# 20key.net
KiCad netlist of a schematic drawn in Altium Designer
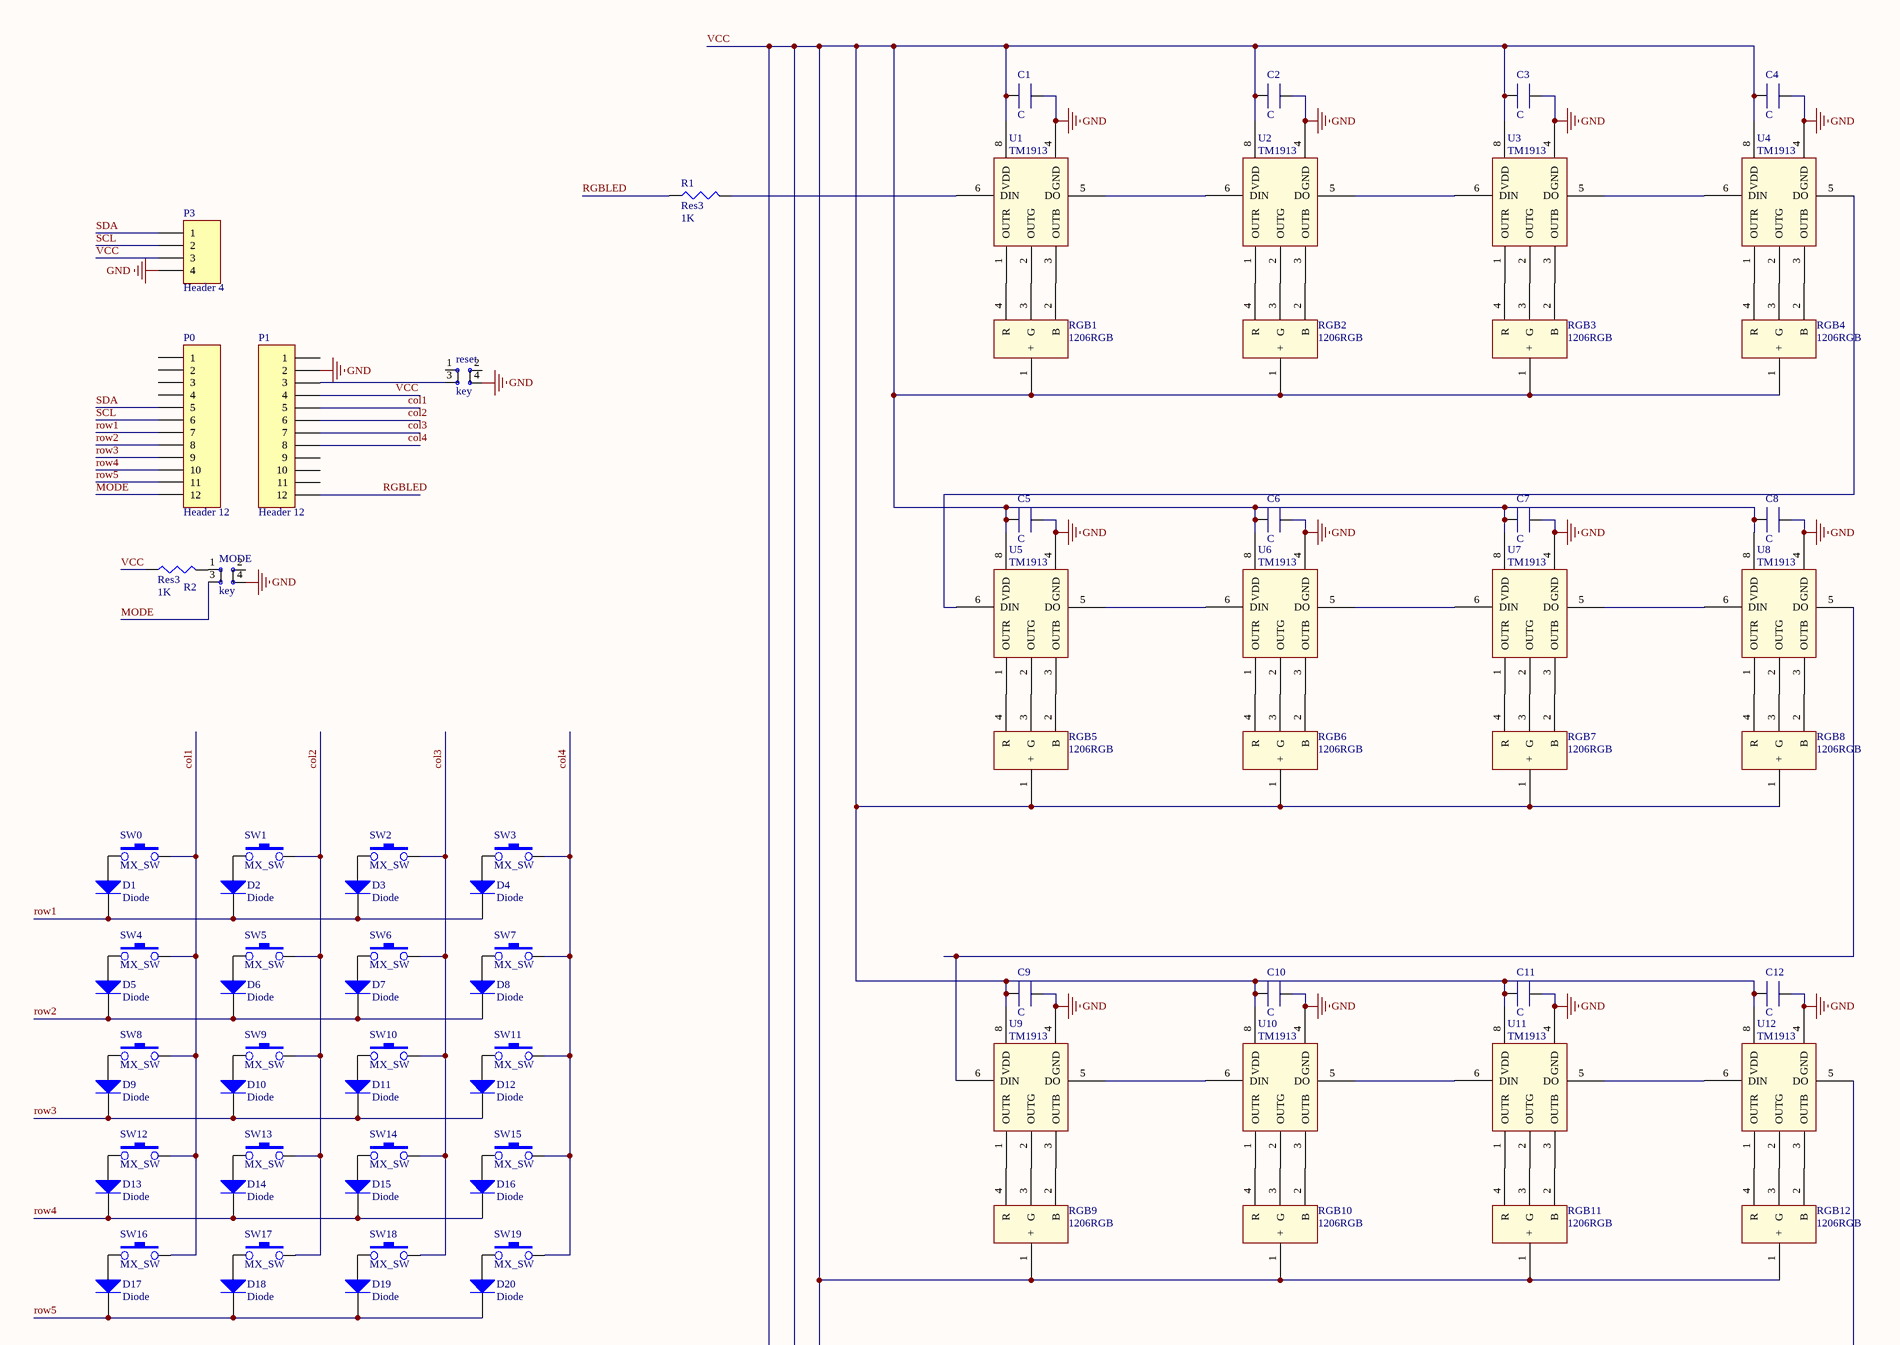
[diagram p0: 20key.SchDoc, top]
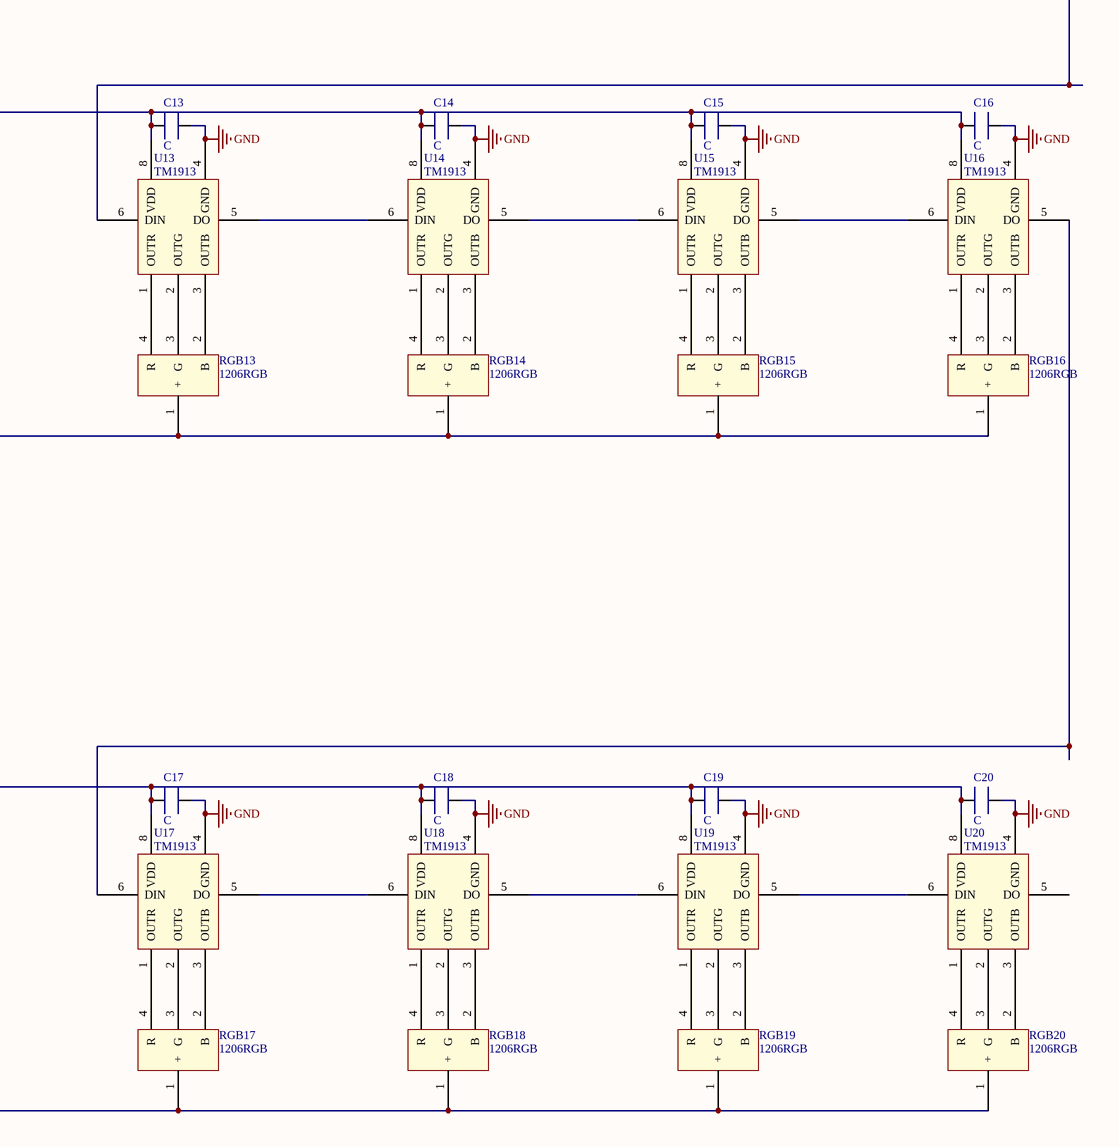
[diagram p1: 20key.SchDoc, bottom]

(export (version "E")
  (design (tool "Eeschema 10.0.6"))
  (components
    (comp (ref "C1") (value "C") (footprint "PCBComponent_1") (libsource (lib "20key") (part "C")))
    (comp (ref "C2") (value "C") (footprint "PCBComponent_1") (libsource (lib "20key") (part "C")))
    (comp (ref "C3") (value "C") (footprint "PCBComponent_1") (libsource (lib "20key") (part "C")))
    (comp (ref "C4") (value "C") (footprint "PCBComponent_1") (libsource (lib "20key") (part "C")))
    (comp (ref "C5") (value "C") (footprint "PCBComponent_1") (libsource (lib "20key") (part "C")))
    (comp (ref "C6") (value "C") (footprint "PCBComponent_1") (libsource (lib "20key") (part "C")))
    (comp (ref "C7") (value "C") (footprint "PCBComponent_1") (libsource (lib "20key") (part "C")))
    (comp (ref "C8") (value "C") (footprint "PCBComponent_1") (libsource (lib "20key") (part "C")))
    (comp (ref "C9") (value "C") (footprint "PCBComponent_1") (libsource (lib "20key") (part "C")))
    (comp (ref "C10") (value "C") (footprint "PCBComponent_1") (libsource (lib "20key") (part "C")))
    (comp (ref "C11") (value "C") (footprint "PCBComponent_1") (libsource (lib "20key") (part "C")))
    (comp (ref "C12") (value "C") (footprint "PCBComponent_1") (libsource (lib "20key") (part "C")))
    (comp (ref "C13") (value "C") (footprint "PCBComponent_1") (libsource (lib "20key") (part "C")))
    (comp (ref "C14") (value "C") (footprint "PCBComponent_1") (libsource (lib "20key") (part "C")))
    (comp (ref "C15") (value "C") (footprint "PCBComponent_1") (libsource (lib "20key") (part "C")))
    (comp (ref "C16") (value "C") (footprint "PCBComponent_1") (libsource (lib "20key") (part "C")))
    (comp (ref "C17") (value "C") (footprint "PCBComponent_1") (libsource (lib "20key") (part "C")))
    (comp (ref "C18") (value "C") (footprint "PCBComponent_1") (libsource (lib "20key") (part "C")))
    (comp (ref "C19") (value "C") (footprint "PCBComponent_1") (libsource (lib "20key") (part "C")))
    (comp (ref "C20") (value "C") (footprint "PCBComponent_1") (libsource (lib "20key") (part "C")))
    (comp (ref "D1")
      (value "Diode")
      (footprint "SODFL160X77-2M")
      (description "Default Diode")
      (fields (field (name "PUBLISHER") "Altium Limited"))
      (libsource (lib "20key") (part "Diode_1"))
    )
    (comp (ref "D2")
      (value "Diode")
      (footprint "SODFL160X77-2M")
      (description "Default Diode")
      (fields (field (name "PUBLISHER") "Altium Limited"))
      (libsource (lib "20key") (part "Diode_1"))
    )
    (comp (ref "D3")
      (value "Diode")
      (footprint "SODFL160X77-2M")
      (description "Default Diode")
      (fields (field (name "PUBLISHER") "Altium Limited"))
      (libsource (lib "20key") (part "Diode_1"))
    )
    (comp (ref "D4")
      (value "Diode")
      (footprint "SODFL160X77-2M")
      (description "Default Diode")
      (fields (field (name "PUBLISHER") "Altium Limited"))
      (libsource (lib "20key") (part "Diode_1"))
    )
    (comp (ref "D5")
      (value "Diode")
      (footprint "SODFL160X77-2M")
      (description "Default Diode")
      (fields (field (name "PUBLISHER") "Altium Limited"))
      (libsource (lib "20key") (part "Diode_1"))
    )
    (comp (ref "D6")
      (value "Diode")
      (footprint "SODFL160X77-2M")
      (description "Default Diode")
      (fields (field (name "PUBLISHER") "Altium Limited"))
      (libsource (lib "20key") (part "Diode_1"))
    )
    (comp (ref "D7")
      (value "Diode")
      (footprint "SODFL160X77-2M")
      (description "Default Diode")
      (fields (field (name "PUBLISHER") "Altium Limited"))
      (libsource (lib "20key") (part "Diode_1"))
    )
    (comp (ref "D8")
      (value "Diode")
      (footprint "SODFL160X77-2M")
      (description "Default Diode")
      (fields (field (name "PUBLISHER") "Altium Limited"))
      (libsource (lib "20key") (part "Diode_1"))
    )
    (comp (ref "D9")
      (value "Diode")
      (footprint "SODFL160X77-2M")
      (description "Default Diode")
      (fields (field (name "PUBLISHER") "Altium Limited"))
      (libsource (lib "20key") (part "Diode_1"))
    )
    (comp (ref "D10")
      (value "Diode")
      (footprint "SODFL160X77-2M")
      (description "Default Diode")
      (fields (field (name "PUBLISHER") "Altium Limited"))
      (libsource (lib "20key") (part "Diode_1"))
    )
    (comp (ref "D11")
      (value "Diode")
      (footprint "SODFL160X77-2M")
      (description "Default Diode")
      (fields (field (name "PUBLISHER") "Altium Limited"))
      (libsource (lib "20key") (part "Diode_1"))
    )
    (comp (ref "D12")
      (value "Diode")
      (footprint "SODFL160X77-2M")
      (description "Default Diode")
      (fields (field (name "PUBLISHER") "Altium Limited"))
      (libsource (lib "20key") (part "Diode_1"))
    )
    (comp (ref "D13")
      (value "Diode")
      (footprint "SODFL160X77-2M")
      (description "Default Diode")
      (fields (field (name "PUBLISHER") "Altium Limited"))
      (libsource (lib "20key") (part "Diode_1"))
    )
    (comp (ref "D14")
      (value "Diode")
      (footprint "SODFL160X77-2M")
      (description "Default Diode")
      (fields (field (name "PUBLISHER") "Altium Limited"))
      (libsource (lib "20key") (part "Diode_1"))
    )
    (comp (ref "D15")
      (value "Diode")
      (footprint "SODFL160X77-2M")
      (description "Default Diode")
      (fields (field (name "PUBLISHER") "Altium Limited"))
      (libsource (lib "20key") (part "Diode_1"))
    )
    (comp (ref "D16")
      (value "Diode")
      (footprint "SODFL160X77-2M")
      (description "Default Diode")
      (fields (field (name "PUBLISHER") "Altium Limited"))
      (libsource (lib "20key") (part "Diode_1"))
    )
    (comp (ref "D17")
      (value "Diode")
      (footprint "SODFL160X77-2M")
      (description "Default Diode")
      (fields (field (name "PUBLISHER") "Altium Limited"))
      (libsource (lib "20key") (part "Diode_1"))
    )
    (comp (ref "D18")
      (value "Diode")
      (footprint "SODFL160X77-2M")
      (description "Default Diode")
      (fields (field (name "PUBLISHER") "Altium Limited"))
      (libsource (lib "20key") (part "Diode_1"))
    )
    (comp (ref "D19")
      (value "Diode")
      (footprint "SODFL160X77-2M")
      (description "Default Diode")
      (fields (field (name "PUBLISHER") "Altium Limited"))
      (libsource (lib "20key") (part "Diode_1"))
    )
    (comp (ref "D20")
      (value "Diode")
      (footprint "SODFL160X77-2M")
      (description "Default Diode")
      (fields (field (name "PUBLISHER") "Altium Limited"))
      (libsource (lib "20key") (part "Diode_1"))
    )
    (comp (ref "MODE") (value "key") (footprint "PCBComponent_1") (libsource (lib "20key") (part "key")))
    (comp (ref "P0")
      (value "Header 12")
      (footprint "HDR1X12")
      (description "Header, 12-Pin")
      (fields (field (name "PUBLISHER") "Altium Limited"))
      (libsource (lib "") (part "Header 12_1"))
    )
    (comp (ref "P1")
      (value "Header 12")
      (footprint "HDR1X12")
      (description "Header, 12-Pin")
      (fields (field (name "PUBLISHER") "Altium Limited"))
      (libsource (lib "Miscellaneous Connectors") (part "Header 12"))
    )
    (comp (ref "P3")
      (value "Header 4")
      (footprint "HDR1X4")
      (description "Header, 4-Pin")
      (fields (field (name "PUBLISHER") "Altium Limited"))
      (libsource (lib "Miscellaneous Connectors") (part "Header 4"))
    )
    (comp (ref "R1")
      (value "Res3")
      (footprint "J1-0603")
      (description "Resistor")
      (fields (field (name "ALTIUM_VALUE") "1K") (field (name "PUBLISHER") "Altium Limited"))
      (libsource (lib "Miscellaneous Devices") (part "Res3"))
    )
    (comp (ref "R2")
      (value "Res3")
      (footprint "J1-0603")
      (description "Resistor")
      (fields (field (name "ALTIUM_VALUE") "1K") (field (name "PUBLISHER") "Altium Limited"))
      (libsource (lib "Miscellaneous Devices") (part "Res3"))
    )
    (comp (ref "reset") (value "key") (footprint "PCBComponent_1") (libsource (lib "20key") (part "key")))
    (comp (ref "RGB1")
      (value "1206RGB")
      (footprint "CAC-150P150X300-4M")
      (libsource (lib "20key") (part "1206RGB"))
    )
    (comp (ref "RGB2")
      (value "1206RGB")
      (footprint "CAC-150P150X300-4M")
      (libsource (lib "20key") (part "1206RGB"))
    )
    (comp (ref "RGB3")
      (value "1206RGB")
      (footprint "CAC-150P150X300-4M")
      (libsource (lib "20key") (part "1206RGB"))
    )
    (comp (ref "RGB4")
      (value "1206RGB")
      (footprint "CAC-150P150X300-4M")
      (libsource (lib "20key") (part "1206RGB"))
    )
    (comp (ref "RGB5")
      (value "1206RGB")
      (footprint "CAC-150P150X300-4M")
      (libsource (lib "20key") (part "1206RGB"))
    )
    (comp (ref "RGB6")
      (value "1206RGB")
      (footprint "CAC-150P150X300-4M")
      (libsource (lib "20key") (part "1206RGB"))
    )
    (comp (ref "RGB7")
      (value "1206RGB")
      (footprint "CAC-150P150X300-4M")
      (libsource (lib "20key") (part "1206RGB"))
    )
    (comp (ref "RGB8")
      (value "1206RGB")
      (footprint "CAC-150P150X300-4M")
      (libsource (lib "20key") (part "1206RGB"))
    )
    (comp (ref "RGB9")
      (value "1206RGB")
      (footprint "CAC-150P150X300-4M")
      (libsource (lib "20key") (part "1206RGB"))
    )
    (comp (ref "RGB10")
      (value "1206RGB")
      (footprint "CAC-150P150X300-4M")
      (libsource (lib "20key") (part "1206RGB"))
    )
    (comp (ref "RGB11")
      (value "1206RGB")
      (footprint "CAC-150P150X300-4M")
      (libsource (lib "20key") (part "1206RGB"))
    )
    (comp (ref "RGB12")
      (value "1206RGB")
      (footprint "CAC-150P150X300-4M")
      (libsource (lib "20key") (part "1206RGB"))
    )
    (comp (ref "RGB13")
      (value "1206RGB")
      (footprint "CAC-150P150X300-4M")
      (libsource (lib "20key") (part "1206RGB"))
    )
    (comp (ref "RGB14")
      (value "1206RGB")
      (footprint "CAC-150P150X300-4M")
      (libsource (lib "20key") (part "1206RGB"))
    )
    (comp (ref "RGB15")
      (value "1206RGB")
      (footprint "CAC-150P150X300-4M")
      (libsource (lib "20key") (part "1206RGB"))
    )
    (comp (ref "RGB16")
      (value "1206RGB")
      (footprint "CAC-150P150X300-4M")
      (libsource (lib "20key") (part "1206RGB"))
    )
    (comp (ref "RGB17")
      (value "1206RGB")
      (footprint "CAC-150P150X300-4M")
      (libsource (lib "20key") (part "1206RGB"))
    )
    (comp (ref "RGB18")
      (value "1206RGB")
      (footprint "CAC-150P150X300-4M")
      (libsource (lib "20key") (part "1206RGB"))
    )
    (comp (ref "RGB19")
      (value "1206RGB")
      (footprint "CAC-150P150X300-4M")
      (libsource (lib "20key") (part "1206RGB"))
    )
    (comp (ref "RGB20")
      (value "1206RGB")
      (footprint "CAC-150P150X300-4M")
      (libsource (lib "20key") (part "1206RGB"))
    )
    (comp (ref "SW0")
      (value "MX_SW")
      (footprint "MX_SW-4")
      (description "with Fixation pins  1-Pole")
      (libsource (lib "KeyBoard") (part "MX_SW-4"))
    )
    (comp (ref "SW1")
      (value "MX_SW")
      (footprint "MX_SW-4")
      (description "with Fixation pins  1-Pole")
      (libsource (lib "KeyBoard") (part "MX_SW-4"))
    )
    (comp (ref "SW2")
      (value "MX_SW")
      (footprint "MX_SW-4")
      (description "with Fixation pins  1-Pole")
      (libsource (lib "KeyBoard") (part "MX_SW-4"))
    )
    (comp (ref "SW3")
      (value "MX_SW")
      (footprint "MX_SW-4")
      (description "with Fixation pins  1-Pole")
      (libsource (lib "KeyBoard") (part "MX_SW-4"))
    )
    (comp (ref "SW4")
      (value "MX_SW")
      (footprint "MX_SW-4")
      (description "with Fixation pins  1-Pole")
      (libsource (lib "KeyBoard") (part "MX_SW-4"))
    )
    (comp (ref "SW5")
      (value "MX_SW")
      (footprint "MX_SW-4")
      (description "with Fixation pins  1-Pole")
      (libsource (lib "KeyBoard") (part "MX_SW-4"))
    )
    (comp (ref "SW6")
      (value "MX_SW")
      (footprint "MX_SW-4")
      (description "with Fixation pins  1-Pole")
      (libsource (lib "KeyBoard") (part "MX_SW-4"))
    )
    (comp (ref "SW7")
      (value "MX_SW")
      (footprint "MX_SW-4")
      (description "with Fixation pins  1-Pole")
      (libsource (lib "KeyBoard") (part "MX_SW-4"))
    )
    (comp (ref "SW8")
      (value "MX_SW")
      (footprint "MX_SW-4")
      (description "with Fixation pins  1-Pole")
      (libsource (lib "KeyBoard") (part "MX_SW-4"))
    )
    (comp (ref "SW9")
      (value "MX_SW")
      (footprint "MX_SW-4")
      (description "with Fixation pins  1-Pole")
      (libsource (lib "KeyBoard") (part "MX_SW-4"))
    )
    (comp (ref "SW10")
      (value "MX_SW")
      (footprint "MX_SW-4")
      (description "with Fixation pins  1-Pole")
      (libsource (lib "KeyBoard") (part "MX_SW-4"))
    )
    (comp (ref "SW11")
      (value "MX_SW")
      (footprint "MX_SW-4")
      (description "with Fixation pins  1-Pole")
      (libsource (lib "KeyBoard") (part "MX_SW-4"))
    )
    (comp (ref "SW12")
      (value "MX_SW")
      (footprint "MX_SW-4")
      (description "with Fixation pins  1-Pole")
      (libsource (lib "KeyBoard") (part "MX_SW-4"))
    )
    (comp (ref "SW13")
      (value "MX_SW")
      (footprint "MX_SW-4")
      (description "with Fixation pins  1-Pole")
      (libsource (lib "KeyBoard") (part "MX_SW-4"))
    )
    (comp (ref "SW14")
      (value "MX_SW")
      (footprint "MX_SW-4")
      (description "with Fixation pins  1-Pole")
      (libsource (lib "KeyBoard") (part "MX_SW-4"))
    )
    (comp (ref "SW15")
      (value "MX_SW")
      (footprint "MX_SW-4")
      (description "with Fixation pins  1-Pole")
      (libsource (lib "KeyBoard") (part "MX_SW-4"))
    )
    (comp (ref "SW16")
      (value "MX_SW")
      (footprint "MX_SW-4")
      (description "with Fixation pins  1-Pole")
      (libsource (lib "KeyBoard") (part "MX_SW-4"))
    )
    (comp (ref "SW17")
      (value "MX_SW")
      (footprint "MX_SW-4")
      (description "with Fixation pins  1-Pole")
      (libsource (lib "KeyBoard") (part "MX_SW-4"))
    )
    (comp (ref "SW18")
      (value "MX_SW")
      (footprint "MX_SW-4")
      (description "with Fixation pins  1-Pole")
      (libsource (lib "KeyBoard") (part "MX_SW-4"))
    )
    (comp (ref "SW19")
      (value "MX_SW")
      (footprint "MX_SW-4")
      (description "with Fixation pins  1-Pole")
      (libsource (lib "KeyBoard") (part "MX_SW-4"))
    )
    (comp (ref "U1")
      (value "TM1913")
      (footprint "SOP127P600X175-8L")
      (libsource (lib "20key") (part "TM1913"))
    )
    (comp (ref "U2")
      (value "TM1913")
      (footprint "SOP127P600X175-8L")
      (libsource (lib "20key") (part "TM1913"))
    )
    (comp (ref "U3")
      (value "TM1913")
      (footprint "SOP127P600X175-8L")
      (libsource (lib "20key") (part "TM1913"))
    )
    (comp (ref "U4")
      (value "TM1913")
      (footprint "SOP127P600X175-8L")
      (libsource (lib "20key") (part "TM1913"))
    )
    (comp (ref "U5")
      (value "TM1913")
      (footprint "SOP127P600X175-8L")
      (libsource (lib "20key") (part "TM1913"))
    )
    (comp (ref "U6")
      (value "TM1913")
      (footprint "SOP127P600X175-8L")
      (libsource (lib "20key") (part "TM1913"))
    )
    (comp (ref "U7")
      (value "TM1913")
      (footprint "SOP127P600X175-8L")
      (libsource (lib "20key") (part "TM1913"))
    )
    (comp (ref "U8")
      (value "TM1913")
      (footprint "SOP127P600X175-8L")
      (libsource (lib "20key") (part "TM1913"))
    )
    (comp (ref "U9")
      (value "TM1913")
      (footprint "SOP127P600X175-8L")
      (libsource (lib "20key") (part "TM1913"))
    )
    (comp (ref "U10")
      (value "TM1913")
      (footprint "SOP127P600X175-8L")
      (libsource (lib "20key") (part "TM1913"))
    )
    (comp (ref "U11")
      (value "TM1913")
      (footprint "SOP127P600X175-8L")
      (libsource (lib "20key") (part "TM1913"))
    )
    (comp (ref "U12")
      (value "TM1913")
      (footprint "SOP127P600X175-8L")
      (libsource (lib "20key") (part "TM1913"))
    )
    (comp (ref "U13")
      (value "TM1913")
      (footprint "SOP127P600X175-8L")
      (libsource (lib "20key") (part "TM1913"))
    )
    (comp (ref "U14")
      (value "TM1913")
      (footprint "SOP127P600X175-8L")
      (libsource (lib "20key") (part "TM1913"))
    )
    (comp (ref "U15")
      (value "TM1913")
      (footprint "SOP127P600X175-8L")
      (libsource (lib "20key") (part "TM1913"))
    )
    (comp (ref "U16")
      (value "TM1913")
      (footprint "SOP127P600X175-8L")
      (libsource (lib "20key") (part "TM1913"))
    )
    (comp (ref "U17")
      (value "TM1913")
      (footprint "SOP127P600X175-8L")
      (libsource (lib "20key") (part "TM1913"))
    )
    (comp (ref "U18")
      (value "TM1913")
      (footprint "SOP127P600X175-8L")
      (libsource (lib "20key") (part "TM1913"))
    )
    (comp (ref "U19")
      (value "TM1913")
      (footprint "SOP127P600X175-8L")
      (libsource (lib "20key") (part "TM1913"))
    )
    (comp (ref "U20")
      (value "TM1913")
      (footprint "SOP127P600X175-8L")
      (libsource (lib "20key") (part "TM1913"))
    )
  )
  (nets
    (net (code "1") (name "/MODE") (class "Default")
      (node (ref "MODE") (pin "3") (pinfunction "A_3") (pintype "passive"))
      (node (ref "P0") (pin "12") (pinfunction "12_12") (pintype "passive"))
    )
    (net (code "2") (name "/RGBLED") (class "Default")
      (node (ref "P1") (pin "12") (pinfunction "12_12") (pintype "passive"))
      (node (ref "R1") (pin "1") (pinfunction "1_1") (pintype "passive"))
    )
    (net (code "3") (name "/SCL") (class "Default")
      (node (ref "P0") (pin "6") (pinfunction "6_6") (pintype "passive"))
      (node (ref "P3") (pin "2") (pinfunction "2_2") (pintype "passive"))
    )
    (net (code "4") (name "/SDA") (class "Default")
      (node (ref "P0") (pin "5") (pinfunction "5_5") (pintype "passive"))
      (node (ref "P3") (pin "1") (pinfunction "1_1") (pintype "passive"))
    )
    (net (code "5") (name "/VCC") (class "Default")
      (node (ref "C1") (pin "1") (pinfunction "1_1") (pintype "passive"))
      (node (ref "C10") (pin "1") (pinfunction "1_1") (pintype "passive"))
      (node (ref "C11") (pin "1") (pinfunction "1_1") (pintype "passive"))
      (node (ref "C12") (pin "1") (pinfunction "1_1") (pintype "passive"))
      (node (ref "C13") (pin "1") (pinfunction "1_1") (pintype "passive"))
      (node (ref "C14") (pin "1") (pinfunction "1_1") (pintype "passive"))
      (node (ref "C15") (pin "1") (pinfunction "1_1") (pintype "passive"))
      (node (ref "C16") (pin "1") (pinfunction "1_1") (pintype "passive"))
      (node (ref "C17") (pin "1") (pinfunction "1_1") (pintype "passive"))
      (node (ref "C18") (pin "1") (pinfunction "1_1") (pintype "passive"))
      (node (ref "C19") (pin "1") (pinfunction "1_1") (pintype "passive"))
      (node (ref "C2") (pin "1") (pinfunction "1_1") (pintype "passive"))
      (node (ref "C20") (pin "1") (pinfunction "1_1") (pintype "passive"))
      (node (ref "C3") (pin "1") (pinfunction "1_1") (pintype "passive"))
      (node (ref "C4") (pin "1") (pinfunction "1_1") (pintype "passive"))
      (node (ref "C5") (pin "1") (pinfunction "1_1") (pintype "passive"))
      (node (ref "C6") (pin "1") (pinfunction "1_1") (pintype "passive"))
      (node (ref "C7") (pin "1") (pinfunction "1_1") (pintype "passive"))
      (node (ref "C8") (pin "1") (pinfunction "1_1") (pintype "passive"))
      (node (ref "C9") (pin "1") (pinfunction "1_1") (pintype "passive"))
      (node (ref "P1") (pin "4") (pinfunction "4_4") (pintype "passive"))
      (node (ref "P3") (pin "3") (pinfunction "3_3") (pintype "passive"))
      (node (ref "R2") (pin "1") (pinfunction "1_1") (pintype "passive"))
      (node (ref "RGB1") (pin "1") (pinfunction "+_1") (pintype "passive"))
      (node (ref "RGB10") (pin "1") (pinfunction "+_1") (pintype "passive"))
      (node (ref "RGB11") (pin "1") (pinfunction "+_1") (pintype "passive"))
      (node (ref "RGB12") (pin "1") (pinfunction "+_1") (pintype "passive"))
      (node (ref "RGB13") (pin "1") (pinfunction "+_1") (pintype "passive"))
      (node (ref "RGB14") (pin "1") (pinfunction "+_1") (pintype "passive"))
      (node (ref "RGB15") (pin "1") (pinfunction "+_1") (pintype "passive"))
      (node (ref "RGB16") (pin "1") (pinfunction "+_1") (pintype "passive"))
      (node (ref "RGB17") (pin "1") (pinfunction "+_1") (pintype "passive"))
      (node (ref "RGB18") (pin "1") (pinfunction "+_1") (pintype "passive"))
      (node (ref "RGB19") (pin "1") (pinfunction "+_1") (pintype "passive"))
      (node (ref "RGB2") (pin "1") (pinfunction "+_1") (pintype "passive"))
      (node (ref "RGB20") (pin "1") (pinfunction "+_1") (pintype "passive"))
      (node (ref "RGB3") (pin "1") (pinfunction "+_1") (pintype "passive"))
      (node (ref "RGB4") (pin "1") (pinfunction "+_1") (pintype "passive"))
      (node (ref "RGB5") (pin "1") (pinfunction "+_1") (pintype "passive"))
      (node (ref "RGB6") (pin "1") (pinfunction "+_1") (pintype "passive"))
      (node (ref "RGB7") (pin "1") (pinfunction "+_1") (pintype "passive"))
      (node (ref "RGB8") (pin "1") (pinfunction "+_1") (pintype "passive"))
      (node (ref "RGB9") (pin "1") (pinfunction "+_1") (pintype "passive"))
      (node (ref "U1") (pin "8") (pinfunction "VDD_8") (pintype "passive"))
      (node (ref "U10") (pin "8") (pinfunction "VDD_8") (pintype "passive"))
      (node (ref "U11") (pin "8") (pinfunction "VDD_8") (pintype "passive"))
      (node (ref "U12") (pin "8") (pinfunction "VDD_8") (pintype "passive"))
      (node (ref "U13") (pin "8") (pinfunction "VDD_8") (pintype "passive"))
      (node (ref "U14") (pin "8") (pinfunction "VDD_8") (pintype "passive"))
      (node (ref "U15") (pin "8") (pinfunction "VDD_8") (pintype "passive"))
      (node (ref "U16") (pin "8") (pinfunction "VDD_8") (pintype "passive"))
      (node (ref "U17") (pin "8") (pinfunction "VDD_8") (pintype "passive"))
      (node (ref "U18") (pin "8") (pinfunction "VDD_8") (pintype "passive"))
      (node (ref "U19") (pin "8") (pinfunction "VDD_8") (pintype "passive"))
      (node (ref "U2") (pin "8") (pinfunction "VDD_8") (pintype "passive"))
      (node (ref "U20") (pin "8") (pinfunction "VDD_8") (pintype "passive"))
      (node (ref "U3") (pin "8") (pinfunction "VDD_8") (pintype "passive"))
      (node (ref "U4") (pin "8") (pinfunction "VDD_8") (pintype "passive"))
      (node (ref "U5") (pin "8") (pinfunction "VDD_8") (pintype "passive"))
      (node (ref "U6") (pin "8") (pinfunction "VDD_8") (pintype "passive"))
      (node (ref "U7") (pin "8") (pinfunction "VDD_8") (pintype "passive"))
      (node (ref "U8") (pin "8") (pinfunction "VDD_8") (pintype "passive"))
      (node (ref "U9") (pin "8") (pinfunction "VDD_8") (pintype "passive"))
    )
    (net (code "6") (name "/col1") (class "Default")
      (node (ref "P1") (pin "5") (pinfunction "5_5") (pintype "passive"))
      (node (ref "SW0") (pin "2") (pinfunction "2_2") (pintype "passive"))
      (node (ref "SW12") (pin "2") (pinfunction "2_2") (pintype "passive"))
      (node (ref "SW16") (pin "2") (pinfunction "2_2") (pintype "passive"))
      (node (ref "SW4") (pin "2") (pinfunction "2_2") (pintype "passive"))
      (node (ref "SW8") (pin "2") (pinfunction "2_2") (pintype "passive"))
    )
    (net (code "7") (name "/col2") (class "Default")
      (node (ref "P1") (pin "6") (pinfunction "6_6") (pintype "passive"))
      (node (ref "SW1") (pin "2") (pinfunction "2_2") (pintype "passive"))
      (node (ref "SW13") (pin "2") (pinfunction "2_2") (pintype "passive"))
      (node (ref "SW17") (pin "2") (pinfunction "2_2") (pintype "passive"))
      (node (ref "SW5") (pin "2") (pinfunction "2_2") (pintype "passive"))
      (node (ref "SW9") (pin "2") (pinfunction "2_2") (pintype "passive"))
    )
    (net (code "8") (name "/col3") (class "Default")
      (node (ref "P1") (pin "7") (pinfunction "7_7") (pintype "passive"))
      (node (ref "SW10") (pin "2") (pinfunction "2_2") (pintype "passive"))
      (node (ref "SW14") (pin "2") (pinfunction "2_2") (pintype "passive"))
      (node (ref "SW18") (pin "2") (pinfunction "2_2") (pintype "passive"))
      (node (ref "SW2") (pin "2") (pinfunction "2_2") (pintype "passive"))
      (node (ref "SW6") (pin "2") (pinfunction "2_2") (pintype "passive"))
    )
    (net (code "9") (name "/col4") (class "Default")
      (node (ref "P1") (pin "8") (pinfunction "8_8") (pintype "passive"))
      (node (ref "SW11") (pin "2") (pinfunction "2_2") (pintype "passive"))
      (node (ref "SW15") (pin "2") (pinfunction "2_2") (pintype "passive"))
      (node (ref "SW19") (pin "2") (pinfunction "2_2") (pintype "passive"))
      (node (ref "SW3") (pin "2") (pinfunction "2_2") (pintype "passive"))
      (node (ref "SW7") (pin "2") (pinfunction "2_2") (pintype "passive"))
    )
    (net (code "10") (name "/row1") (class "Default")
      (node (ref "D1") (pin "1") (pinfunction "K_1") (pintype "passive"))
      (node (ref "D2") (pin "1") (pinfunction "K_1") (pintype "passive"))
      (node (ref "D3") (pin "1") (pinfunction "K_1") (pintype "passive"))
      (node (ref "D4") (pin "1") (pinfunction "K_1") (pintype "passive"))
      (node (ref "P0") (pin "7") (pinfunction "7_7") (pintype "passive"))
    )
    (net (code "11") (name "/row2") (class "Default")
      (node (ref "D5") (pin "1") (pinfunction "K_1") (pintype "passive"))
      (node (ref "D6") (pin "1") (pinfunction "K_1") (pintype "passive"))
      (node (ref "D7") (pin "1") (pinfunction "K_1") (pintype "passive"))
      (node (ref "D8") (pin "1") (pinfunction "K_1") (pintype "passive"))
      (node (ref "P0") (pin "8") (pinfunction "8_8") (pintype "passive"))
    )
    (net (code "12") (name "/row3") (class "Default")
      (node (ref "D10") (pin "1") (pinfunction "K_1") (pintype "passive"))
      (node (ref "D11") (pin "1") (pinfunction "K_1") (pintype "passive"))
      (node (ref "D12") (pin "1") (pinfunction "K_1") (pintype "passive"))
      (node (ref "D9") (pin "1") (pinfunction "K_1") (pintype "passive"))
      (node (ref "P0") (pin "9") (pinfunction "9_9") (pintype "passive"))
    )
    (net (code "13") (name "/row4") (class "Default")
      (node (ref "D13") (pin "1") (pinfunction "K_1") (pintype "passive"))
      (node (ref "D14") (pin "1") (pinfunction "K_1") (pintype "passive"))
      (node (ref "D15") (pin "1") (pinfunction "K_1") (pintype "passive"))
      (node (ref "D16") (pin "1") (pinfunction "K_1") (pintype "passive"))
      (node (ref "P0") (pin "10") (pinfunction "10_10") (pintype "passive"))
    )
    (net (code "14") (name "/row5") (class "Default")
      (node (ref "D17") (pin "1") (pinfunction "K_1") (pintype "passive"))
      (node (ref "D18") (pin "1") (pinfunction "K_1") (pintype "passive"))
      (node (ref "D19") (pin "1") (pinfunction "K_1") (pintype "passive"))
      (node (ref "D20") (pin "1") (pinfunction "K_1") (pintype "passive"))
      (node (ref "P0") (pin "11") (pinfunction "11_11") (pintype "passive"))
    )
    (net (code "15") (name "GND") (class "Default")
      (node (ref "C1") (pin "2") (pinfunction "2_2") (pintype "passive"))
      (node (ref "C10") (pin "2") (pinfunction "2_2") (pintype "passive"))
      (node (ref "C11") (pin "2") (pinfunction "2_2") (pintype "passive"))
      (node (ref "C12") (pin "2") (pinfunction "2_2") (pintype "passive"))
      (node (ref "C13") (pin "2") (pinfunction "2_2") (pintype "passive"))
      (node (ref "C14") (pin "2") (pinfunction "2_2") (pintype "passive"))
      (node (ref "C15") (pin "2") (pinfunction "2_2") (pintype "passive"))
      (node (ref "C16") (pin "2") (pinfunction "2_2") (pintype "passive"))
      (node (ref "C17") (pin "2") (pinfunction "2_2") (pintype "passive"))
      (node (ref "C18") (pin "2") (pinfunction "2_2") (pintype "passive"))
      (node (ref "C19") (pin "2") (pinfunction "2_2") (pintype "passive"))
      (node (ref "C2") (pin "2") (pinfunction "2_2") (pintype "passive"))
      (node (ref "C20") (pin "2") (pinfunction "2_2") (pintype "passive"))
      (node (ref "C3") (pin "2") (pinfunction "2_2") (pintype "passive"))
      (node (ref "C4") (pin "2") (pinfunction "2_2") (pintype "passive"))
      (node (ref "C5") (pin "2") (pinfunction "2_2") (pintype "passive"))
      (node (ref "C6") (pin "2") (pinfunction "2_2") (pintype "passive"))
      (node (ref "C7") (pin "2") (pinfunction "2_2") (pintype "passive"))
      (node (ref "C8") (pin "2") (pinfunction "2_2") (pintype "passive"))
      (node (ref "C9") (pin "2") (pinfunction "2_2") (pintype "passive"))
      (node (ref "MODE") (pin "4") (pinfunction "B_4") (pintype "passive"))
      (node (ref "P1") (pin "2") (pinfunction "2_2") (pintype "passive"))
      (node (ref "P3") (pin "4") (pinfunction "4_4") (pintype "passive"))
      (node (ref "U1") (pin "4") (pinfunction "GND_4") (pintype "passive"))
      (node (ref "U10") (pin "4") (pinfunction "GND_4") (pintype "passive"))
      (node (ref "U11") (pin "4") (pinfunction "GND_4") (pintype "passive"))
      (node (ref "U12") (pin "4") (pinfunction "GND_4") (pintype "passive"))
      (node (ref "U13") (pin "4") (pinfunction "GND_4") (pintype "passive"))
      (node (ref "U14") (pin "4") (pinfunction "GND_4") (pintype "passive"))
      (node (ref "U15") (pin "4") (pinfunction "GND_4") (pintype "passive"))
      (node (ref "U16") (pin "4") (pinfunction "GND_4") (pintype "passive"))
      (node (ref "U17") (pin "4") (pinfunction "GND_4") (pintype "passive"))
      (node (ref "U18") (pin "4") (pinfunction "GND_4") (pintype "passive"))
      (node (ref "U19") (pin "4") (pinfunction "GND_4") (pintype "passive"))
      (node (ref "U2") (pin "4") (pinfunction "GND_4") (pintype "passive"))
      (node (ref "U20") (pin "4") (pinfunction "GND_4") (pintype "passive"))
      (node (ref "U3") (pin "4") (pinfunction "GND_4") (pintype "passive"))
      (node (ref "U4") (pin "4") (pinfunction "GND_4") (pintype "passive"))
      (node (ref "U5") (pin "4") (pinfunction "GND_4") (pintype "passive"))
      (node (ref "U6") (pin "4") (pinfunction "GND_4") (pintype "passive"))
      (node (ref "U7") (pin "4") (pinfunction "GND_4") (pintype "passive"))
      (node (ref "U8") (pin "4") (pinfunction "GND_4") (pintype "passive"))
      (node (ref "U9") (pin "4") (pinfunction "GND_4") (pintype "passive"))
      (node (ref "reset") (pin "4") (pinfunction "B_4") (pintype "passive"))
    )
    (net (code "16") (name "Net-(D1-A)") (class "Default")
      (node (ref "D1") (pin "2") (pinfunction "A_2") (pintype "passive"))
      (node (ref "SW0") (pin "1") (pinfunction "1_1") (pintype "passive"))
    )
    (net (code "17") (name "Net-(D2-A)") (class "Default")
      (node (ref "D2") (pin "2") (pinfunction "A_2") (pintype "passive"))
      (node (ref "SW1") (pin "1") (pinfunction "1_1") (pintype "passive"))
    )
    (net (code "18") (name "Net-(D3-A)") (class "Default")
      (node (ref "D3") (pin "2") (pinfunction "A_2") (pintype "passive"))
      (node (ref "SW2") (pin "1") (pinfunction "1_1") (pintype "passive"))
    )
    (net (code "19") (name "Net-(D4-A)") (class "Default")
      (node (ref "D4") (pin "2") (pinfunction "A_2") (pintype "passive"))
      (node (ref "SW3") (pin "1") (pinfunction "1_1") (pintype "passive"))
    )
    (net (code "20") (name "Net-(D5-A)") (class "Default")
      (node (ref "D5") (pin "2") (pinfunction "A_2") (pintype "passive"))
      (node (ref "SW4") (pin "1") (pinfunction "1_1") (pintype "passive"))
    )
    (net (code "21") (name "Net-(D6-A)") (class "Default")
      (node (ref "D6") (pin "2") (pinfunction "A_2") (pintype "passive"))
      (node (ref "SW5") (pin "1") (pinfunction "1_1") (pintype "passive"))
    )
    (net (code "22") (name "Net-(D7-A)") (class "Default")
      (node (ref "D7") (pin "2") (pinfunction "A_2") (pintype "passive"))
      (node (ref "SW6") (pin "1") (pinfunction "1_1") (pintype "passive"))
    )
    (net (code "23") (name "Net-(D8-A)") (class "Default")
      (node (ref "D8") (pin "2") (pinfunction "A_2") (pintype "passive"))
      (node (ref "SW7") (pin "1") (pinfunction "1_1") (pintype "passive"))
    )
    (net (code "24") (name "Net-(D9-A)") (class "Default")
      (node (ref "D9") (pin "2") (pinfunction "A_2") (pintype "passive"))
      (node (ref "SW8") (pin "1") (pinfunction "1_1") (pintype "passive"))
    )
    (net (code "25") (name "Net-(D10-A)") (class "Default")
      (node (ref "D10") (pin "2") (pinfunction "A_2") (pintype "passive"))
      (node (ref "SW9") (pin "1") (pinfunction "1_1") (pintype "passive"))
    )
    (net (code "26") (name "Net-(D11-A)") (class "Default")
      (node (ref "D11") (pin "2") (pinfunction "A_2") (pintype "passive"))
      (node (ref "SW10") (pin "1") (pinfunction "1_1") (pintype "passive"))
    )
    (net (code "27") (name "Net-(D12-A)") (class "Default")
      (node (ref "D12") (pin "2") (pinfunction "A_2") (pintype "passive"))
      (node (ref "SW11") (pin "1") (pinfunction "1_1") (pintype "passive"))
    )
    (net (code "28") (name "Net-(D13-A)") (class "Default")
      (node (ref "D13") (pin "2") (pinfunction "A_2") (pintype "passive"))
      (node (ref "SW12") (pin "1") (pinfunction "1_1") (pintype "passive"))
    )
    (net (code "29") (name "Net-(D14-A)") (class "Default")
      (node (ref "D14") (pin "2") (pinfunction "A_2") (pintype "passive"))
      (node (ref "SW13") (pin "1") (pinfunction "1_1") (pintype "passive"))
    )
    (net (code "30") (name "Net-(D15-A)") (class "Default")
      (node (ref "D15") (pin "2") (pinfunction "A_2") (pintype "passive"))
      (node (ref "SW14") (pin "1") (pinfunction "1_1") (pintype "passive"))
    )
    (net (code "31") (name "Net-(D16-A)") (class "Default")
      (node (ref "D16") (pin "2") (pinfunction "A_2") (pintype "passive"))
      (node (ref "SW15") (pin "1") (pinfunction "1_1") (pintype "passive"))
    )
    (net (code "32") (name "Net-(D17-A)") (class "Default")
      (node (ref "D17") (pin "2") (pinfunction "A_2") (pintype "passive"))
      (node (ref "SW16") (pin "1") (pinfunction "1_1") (pintype "passive"))
    )
    (net (code "33") (name "Net-(D18-A)") (class "Default")
      (node (ref "D18") (pin "2") (pinfunction "A_2") (pintype "passive"))
      (node (ref "SW17") (pin "1") (pinfunction "1_1") (pintype "passive"))
    )
    (net (code "34") (name "Net-(D19-A)") (class "Default")
      (node (ref "D19") (pin "2") (pinfunction "A_2") (pintype "passive"))
      (node (ref "SW18") (pin "1") (pinfunction "1_1") (pintype "passive"))
    )
    (net (code "35") (name "Net-(D20-A)") (class "Default")
      (node (ref "D20") (pin "2") (pinfunction "A_2") (pintype "passive"))
      (node (ref "SW19") (pin "1") (pinfunction "1_1") (pintype "passive"))
    )
    (net (code "36") (name "Net-(MODE-A-Pad1)") (class "Default")
      (node (ref "MODE") (pin "1") (pinfunction "A_1") (pintype "passive"))
      (node (ref "R2") (pin "2") (pinfunction "2_2") (pintype "passive"))
    )
    (net (code "37") (name "Net-(P1-Pad3)") (class "Default")
      (node (ref "P1") (pin "3") (pinfunction "3_3") (pintype "passive"))
      (node (ref "reset") (pin "3") (pinfunction "A_3") (pintype "passive"))
    )
    (net (code "38") (name "Net-(RGB1-B)") (class "Default")
      (node (ref "RGB1") (pin "2") (pinfunction "B_2") (pintype "passive"))
      (node (ref "U1") (pin "3") (pinfunction "OUTB_3") (pintype "passive"))
    )
    (net (code "39") (name "Net-(RGB1-G)") (class "Default")
      (node (ref "RGB1") (pin "3") (pinfunction "G_3") (pintype "passive"))
      (node (ref "U1") (pin "2") (pinfunction "OUTG_2") (pintype "passive"))
    )
    (net (code "40") (name "Net-(RGB1-R)") (class "Default")
      (node (ref "RGB1") (pin "4") (pinfunction "R_4") (pintype "passive"))
      (node (ref "U1") (pin "1") (pinfunction "OUTR_1") (pintype "passive"))
    )
    (net (code "41") (name "Net-(RGB2-B)") (class "Default")
      (node (ref "RGB2") (pin "2") (pinfunction "B_2") (pintype "passive"))
      (node (ref "U2") (pin "3") (pinfunction "OUTB_3") (pintype "passive"))
    )
    (net (code "42") (name "Net-(RGB2-G)") (class "Default")
      (node (ref "RGB2") (pin "3") (pinfunction "G_3") (pintype "passive"))
      (node (ref "U2") (pin "2") (pinfunction "OUTG_2") (pintype "passive"))
    )
    (net (code "43") (name "Net-(RGB2-R)") (class "Default")
      (node (ref "RGB2") (pin "4") (pinfunction "R_4") (pintype "passive"))
      (node (ref "U2") (pin "1") (pinfunction "OUTR_1") (pintype "passive"))
    )
    (net (code "44") (name "Net-(RGB3-B)") (class "Default")
      (node (ref "RGB3") (pin "2") (pinfunction "B_2") (pintype "passive"))
      (node (ref "U3") (pin "3") (pinfunction "OUTB_3") (pintype "passive"))
    )
    (net (code "45") (name "Net-(RGB3-G)") (class "Default")
      (node (ref "RGB3") (pin "3") (pinfunction "G_3") (pintype "passive"))
      (node (ref "U3") (pin "2") (pinfunction "OUTG_2") (pintype "passive"))
    )
    (net (code "46") (name "Net-(RGB3-R)") (class "Default")
      (node (ref "RGB3") (pin "4") (pinfunction "R_4") (pintype "passive"))
      (node (ref "U3") (pin "1") (pinfunction "OUTR_1") (pintype "passive"))
    )
    (net (code "47") (name "Net-(RGB4-B)") (class "Default")
      (node (ref "RGB4") (pin "2") (pinfunction "B_2") (pintype "passive"))
      (node (ref "U4") (pin "3") (pinfunction "OUTB_3") (pintype "passive"))
    )
    (net (code "48") (name "Net-(RGB4-G)") (class "Default")
      (node (ref "RGB4") (pin "3") (pinfunction "G_3") (pintype "passive"))
      (node (ref "U4") (pin "2") (pinfunction "OUTG_2") (pintype "passive"))
    )
    (net (code "49") (name "Net-(RGB4-R)") (class "Default")
      (node (ref "RGB4") (pin "4") (pinfunction "R_4") (pintype "passive"))
      (node (ref "U4") (pin "1") (pinfunction "OUTR_1") (pintype "passive"))
    )
    (net (code "50") (name "Net-(RGB5-B)") (class "Default")
      (node (ref "RGB5") (pin "2") (pinfunction "B_2") (pintype "passive"))
      (node (ref "U5") (pin "3") (pinfunction "OUTB_3") (pintype "passive"))
    )
    (net (code "51") (name "Net-(RGB5-G)") (class "Default")
      (node (ref "RGB5") (pin "3") (pinfunction "G_3") (pintype "passive"))
      (node (ref "U5") (pin "2") (pinfunction "OUTG_2") (pintype "passive"))
    )
    (net (code "52") (name "Net-(RGB5-R)") (class "Default")
      (node (ref "RGB5") (pin "4") (pinfunction "R_4") (pintype "passive"))
      (node (ref "U5") (pin "1") (pinfunction "OUTR_1") (pintype "passive"))
    )
    (net (code "53") (name "Net-(RGB6-B)") (class "Default")
      (node (ref "RGB6") (pin "2") (pinfunction "B_2") (pintype "passive"))
      (node (ref "U6") (pin "3") (pinfunction "OUTB_3") (pintype "passive"))
    )
    (net (code "54") (name "Net-(RGB6-G)") (class "Default")
      (node (ref "RGB6") (pin "3") (pinfunction "G_3") (pintype "passive"))
      (node (ref "U6") (pin "2") (pinfunction "OUTG_2") (pintype "passive"))
    )
    (net (code "55") (name "Net-(RGB6-R)") (class "Default")
      (node (ref "RGB6") (pin "4") (pinfunction "R_4") (pintype "passive"))
      (node (ref "U6") (pin "1") (pinfunction "OUTR_1") (pintype "passive"))
    )
    (net (code "56") (name "Net-(RGB7-B)") (class "Default")
      (node (ref "RGB7") (pin "2") (pinfunction "B_2") (pintype "passive"))
      (node (ref "U7") (pin "3") (pinfunction "OUTB_3") (pintype "passive"))
    )
    (net (code "57") (name "Net-(RGB7-G)") (class "Default")
      (node (ref "RGB7") (pin "3") (pinfunction "G_3") (pintype "passive"))
      (node (ref "U7") (pin "2") (pinfunction "OUTG_2") (pintype "passive"))
    )
    (net (code "58") (name "Net-(RGB7-R)") (class "Default")
      (node (ref "RGB7") (pin "4") (pinfunction "R_4") (pintype "passive"))
      (node (ref "U7") (pin "1") (pinfunction "OUTR_1") (pintype "passive"))
    )
    (net (code "59") (name "Net-(RGB8-B)") (class "Default")
      (node (ref "RGB8") (pin "2") (pinfunction "B_2") (pintype "passive"))
      (node (ref "U8") (pin "3") (pinfunction "OUTB_3") (pintype "passive"))
    )
    (net (code "60") (name "Net-(RGB8-G)") (class "Default")
      (node (ref "RGB8") (pin "3") (pinfunction "G_3") (pintype "passive"))
      (node (ref "U8") (pin "2") (pinfunction "OUTG_2") (pintype "passive"))
    )
    (net (code "61") (name "Net-(RGB8-R)") (class "Default")
      (node (ref "RGB8") (pin "4") (pinfunction "R_4") (pintype "passive"))
      (node (ref "U8") (pin "1") (pinfunction "OUTR_1") (pintype "passive"))
    )
    (net (code "62") (name "Net-(RGB9-B)") (class "Default")
      (node (ref "RGB9") (pin "2") (pinfunction "B_2") (pintype "passive"))
      (node (ref "U9") (pin "3") (pinfunction "OUTB_3") (pintype "passive"))
    )
    (net (code "63") (name "Net-(RGB9-G)") (class "Default")
      (node (ref "RGB9") (pin "3") (pinfunction "G_3") (pintype "passive"))
      (node (ref "U9") (pin "2") (pinfunction "OUTG_2") (pintype "passive"))
    )
    (net (code "64") (name "Net-(RGB9-R)") (class "Default")
      (node (ref "RGB9") (pin "4") (pinfunction "R_4") (pintype "passive"))
      (node (ref "U9") (pin "1") (pinfunction "OUTR_1") (pintype "passive"))
    )
    (net (code "65") (name "Net-(RGB10-B)") (class "Default")
      (node (ref "RGB10") (pin "2") (pinfunction "B_2") (pintype "passive"))
      (node (ref "U10") (pin "3") (pinfunction "OUTB_3") (pintype "passive"))
    )
    (net (code "66") (name "Net-(RGB10-G)") (class "Default")
      (node (ref "RGB10") (pin "3") (pinfunction "G_3") (pintype "passive"))
      (node (ref "U10") (pin "2") (pinfunction "OUTG_2") (pintype "passive"))
    )
    (net (code "67") (name "Net-(RGB10-R)") (class "Default")
      (node (ref "RGB10") (pin "4") (pinfunction "R_4") (pintype "passive"))
      (node (ref "U10") (pin "1") (pinfunction "OUTR_1") (pintype "passive"))
    )
    (net (code "68") (name "Net-(RGB11-B)") (class "Default")
      (node (ref "RGB11") (pin "2") (pinfunction "B_2") (pintype "passive"))
      (node (ref "U11") (pin "3") (pinfunction "OUTB_3") (pintype "passive"))
    )
    (net (code "69") (name "Net-(RGB11-G)") (class "Default")
      (node (ref "RGB11") (pin "3") (pinfunction "G_3") (pintype "passive"))
      (node (ref "U11") (pin "2") (pinfunction "OUTG_2") (pintype "passive"))
    )
    (net (code "70") (name "Net-(RGB11-R)") (class "Default")
      (node (ref "RGB11") (pin "4") (pinfunction "R_4") (pintype "passive"))
      (node (ref "U11") (pin "1") (pinfunction "OUTR_1") (pintype "passive"))
    )
    (net (code "71") (name "Net-(RGB12-B)") (class "Default")
      (node (ref "RGB12") (pin "2") (pinfunction "B_2") (pintype "passive"))
      (node (ref "U12") (pin "3") (pinfunction "OUTB_3") (pintype "passive"))
    )
    (net (code "72") (name "Net-(RGB12-G)") (class "Default")
      (node (ref "RGB12") (pin "3") (pinfunction "G_3") (pintype "passive"))
      (node (ref "U12") (pin "2") (pinfunction "OUTG_2") (pintype "passive"))
    )
    (net (code "73") (name "Net-(RGB12-R)") (class "Default")
      (node (ref "RGB12") (pin "4") (pinfunction "R_4") (pintype "passive"))
      (node (ref "U12") (pin "1") (pinfunction "OUTR_1") (pintype "passive"))
    )
    (net (code "74") (name "Net-(RGB13-B)") (class "Default")
      (node (ref "RGB13") (pin "2") (pinfunction "B_2") (pintype "passive"))
      (node (ref "U13") (pin "3") (pinfunction "OUTB_3") (pintype "passive"))
    )
    (net (code "75") (name "Net-(RGB13-G)") (class "Default")
      (node (ref "RGB13") (pin "3") (pinfunction "G_3") (pintype "passive"))
      (node (ref "U13") (pin "2") (pinfunction "OUTG_2") (pintype "passive"))
    )
    (net (code "76") (name "Net-(RGB13-R)") (class "Default")
      (node (ref "RGB13") (pin "4") (pinfunction "R_4") (pintype "passive"))
      (node (ref "U13") (pin "1") (pinfunction "OUTR_1") (pintype "passive"))
    )
    (net (code "77") (name "Net-(RGB14-B)") (class "Default")
      (node (ref "RGB14") (pin "2") (pinfunction "B_2") (pintype "passive"))
      (node (ref "U14") (pin "3") (pinfunction "OUTB_3") (pintype "passive"))
    )
    (net (code "78") (name "Net-(RGB14-G)") (class "Default")
      (node (ref "RGB14") (pin "3") (pinfunction "G_3") (pintype "passive"))
      (node (ref "U14") (pin "2") (pinfunction "OUTG_2") (pintype "passive"))
    )
    (net (code "79") (name "Net-(RGB14-R)") (class "Default")
      (node (ref "RGB14") (pin "4") (pinfunction "R_4") (pintype "passive"))
      (node (ref "U14") (pin "1") (pinfunction "OUTR_1") (pintype "passive"))
    )
    (net (code "80") (name "Net-(RGB15-B)") (class "Default")
      (node (ref "RGB15") (pin "2") (pinfunction "B_2") (pintype "passive"))
      (node (ref "U15") (pin "3") (pinfunction "OUTB_3") (pintype "passive"))
    )
    (net (code "81") (name "Net-(RGB15-G)") (class "Default")
      (node (ref "RGB15") (pin "3") (pinfunction "G_3") (pintype "passive"))
      (node (ref "U15") (pin "2") (pinfunction "OUTG_2") (pintype "passive"))
    )
    (net (code "82") (name "Net-(RGB15-R)") (class "Default")
      (node (ref "RGB15") (pin "4") (pinfunction "R_4") (pintype "passive"))
      (node (ref "U15") (pin "1") (pinfunction "OUTR_1") (pintype "passive"))
    )
    (net (code "83") (name "Net-(RGB16-B)") (class "Default")
      (node (ref "RGB16") (pin "2") (pinfunction "B_2") (pintype "passive"))
      (node (ref "U16") (pin "3") (pinfunction "OUTB_3") (pintype "passive"))
    )
    (net (code "84") (name "Net-(RGB16-G)") (class "Default")
      (node (ref "RGB16") (pin "3") (pinfunction "G_3") (pintype "passive"))
      (node (ref "U16") (pin "2") (pinfunction "OUTG_2") (pintype "passive"))
    )
    (net (code "85") (name "Net-(RGB16-R)") (class "Default")
      (node (ref "RGB16") (pin "4") (pinfunction "R_4") (pintype "passive"))
      (node (ref "U16") (pin "1") (pinfunction "OUTR_1") (pintype "passive"))
    )
    (net (code "86") (name "Net-(RGB17-B)") (class "Default")
      (node (ref "RGB17") (pin "2") (pinfunction "B_2") (pintype "passive"))
      (node (ref "U17") (pin "3") (pinfunction "OUTB_3") (pintype "passive"))
    )
    (net (code "87") (name "Net-(RGB17-G)") (class "Default")
      (node (ref "RGB17") (pin "3") (pinfunction "G_3") (pintype "passive"))
      (node (ref "U17") (pin "2") (pinfunction "OUTG_2") (pintype "passive"))
    )
    (net (code "88") (name "Net-(RGB17-R)") (class "Default")
      (node (ref "RGB17") (pin "4") (pinfunction "R_4") (pintype "passive"))
      (node (ref "U17") (pin "1") (pinfunction "OUTR_1") (pintype "passive"))
    )
    (net (code "89") (name "Net-(RGB18-B)") (class "Default")
      (node (ref "RGB18") (pin "2") (pinfunction "B_2") (pintype "passive"))
      (node (ref "U18") (pin "3") (pinfunction "OUTB_3") (pintype "passive"))
    )
    (net (code "90") (name "Net-(RGB18-G)") (class "Default")
      (node (ref "RGB18") (pin "3") (pinfunction "G_3") (pintype "passive"))
      (node (ref "U18") (pin "2") (pinfunction "OUTG_2") (pintype "passive"))
    )
    (net (code "91") (name "Net-(RGB18-R)") (class "Default")
      (node (ref "RGB18") (pin "4") (pinfunction "R_4") (pintype "passive"))
      (node (ref "U18") (pin "1") (pinfunction "OUTR_1") (pintype "passive"))
    )
    (net (code "92") (name "Net-(RGB19-B)") (class "Default")
      (node (ref "RGB19") (pin "2") (pinfunction "B_2") (pintype "passive"))
      (node (ref "U19") (pin "3") (pinfunction "OUTB_3") (pintype "passive"))
    )
    (net (code "93") (name "Net-(RGB19-G)") (class "Default")
      (node (ref "RGB19") (pin "3") (pinfunction "G_3") (pintype "passive"))
      (node (ref "U19") (pin "2") (pinfunction "OUTG_2") (pintype "passive"))
    )
    (net (code "94") (name "Net-(RGB19-R)") (class "Default")
      (node (ref "RGB19") (pin "4") (pinfunction "R_4") (pintype "passive"))
      (node (ref "U19") (pin "1") (pinfunction "OUTR_1") (pintype "passive"))
    )
    (net (code "95") (name "Net-(RGB20-B)") (class "Default")
      (node (ref "RGB20") (pin "2") (pinfunction "B_2") (pintype "passive"))
      (node (ref "U20") (pin "3") (pinfunction "OUTB_3") (pintype "passive"))
    )
    (net (code "96") (name "Net-(RGB20-G)") (class "Default")
      (node (ref "RGB20") (pin "3") (pinfunction "G_3") (pintype "passive"))
      (node (ref "U20") (pin "2") (pinfunction "OUTG_2") (pintype "passive"))
    )
    (net (code "97") (name "Net-(RGB20-R)") (class "Default")
      (node (ref "RGB20") (pin "4") (pinfunction "R_4") (pintype "passive"))
      (node (ref "U20") (pin "1") (pinfunction "OUTR_1") (pintype "passive"))
    )
    (net (code "98") (name "Net-(U1-DIN)") (class "Default")
      (node (ref "R1") (pin "2") (pinfunction "2_2") (pintype "passive"))
      (node (ref "U1") (pin "6") (pinfunction "DIN_6") (pintype "passive"))
    )
    (net (code "99") (name "Net-(U1-DO)") (class "Default")
      (node (ref "U1") (pin "5") (pinfunction "DO_5") (pintype "passive"))
      (node (ref "U2") (pin "6") (pinfunction "DIN_6") (pintype "passive"))
    )
    (net (code "100") (name "Net-(U2-DO)") (class "Default")
      (node (ref "U2") (pin "5") (pinfunction "DO_5") (pintype "passive"))
      (node (ref "U3") (pin "6") (pinfunction "DIN_6") (pintype "passive"))
    )
    (net (code "101") (name "Net-(U3-DO)") (class "Default")
      (node (ref "U3") (pin "5") (pinfunction "DO_5") (pintype "passive"))
      (node (ref "U4") (pin "6") (pinfunction "DIN_6") (pintype "passive"))
    )
    (net (code "102") (name "Net-(U4-DO)") (class "Default")
      (node (ref "U4") (pin "5") (pinfunction "DO_5") (pintype "passive"))
      (node (ref "U5") (pin "6") (pinfunction "DIN_6") (pintype "passive"))
    )
    (net (code "103") (name "Net-(U5-DO)") (class "Default")
      (node (ref "U5") (pin "5") (pinfunction "DO_5") (pintype "passive"))
      (node (ref "U6") (pin "6") (pinfunction "DIN_6") (pintype "passive"))
    )
    (net (code "104") (name "Net-(U6-DO)") (class "Default")
      (node (ref "U6") (pin "5") (pinfunction "DO_5") (pintype "passive"))
      (node (ref "U7") (pin "6") (pinfunction "DIN_6") (pintype "passive"))
    )
    (net (code "105") (name "Net-(U7-DO)") (class "Default")
      (node (ref "U7") (pin "5") (pinfunction "DO_5") (pintype "passive"))
      (node (ref "U8") (pin "6") (pinfunction "DIN_6") (pintype "passive"))
    )
    (net (code "106") (name "Net-(U8-DO)") (class "Default")
      (node (ref "U8") (pin "5") (pinfunction "DO_5") (pintype "passive"))
      (node (ref "U9") (pin "6") (pinfunction "DIN_6") (pintype "passive"))
    )
    (net (code "107") (name "Net-(U10-DIN)") (class "Default")
      (node (ref "U10") (pin "6") (pinfunction "DIN_6") (pintype "passive"))
      (node (ref "U9") (pin "5") (pinfunction "DO_5") (pintype "passive"))
    )
    (net (code "108") (name "Net-(U10-DO)") (class "Default")
      (node (ref "U10") (pin "5") (pinfunction "DO_5") (pintype "passive"))
      (node (ref "U11") (pin "6") (pinfunction "DIN_6") (pintype "passive"))
    )
    (net (code "109") (name "Net-(U11-DO)") (class "Default")
      (node (ref "U11") (pin "5") (pinfunction "DO_5") (pintype "passive"))
      (node (ref "U12") (pin "6") (pinfunction "DIN_6") (pintype "passive"))
    )
    (net (code "110") (name "Net-(U12-DO)") (class "Default")
      (node (ref "U12") (pin "5") (pinfunction "DO_5") (pintype "passive"))
      (node (ref "U13") (pin "6") (pinfunction "DIN_6") (pintype "passive"))
    )
    (net (code "111") (name "Net-(U13-DO)") (class "Default")
      (node (ref "U13") (pin "5") (pinfunction "DO_5") (pintype "passive"))
      (node (ref "U14") (pin "6") (pinfunction "DIN_6") (pintype "passive"))
    )
    (net (code "112") (name "Net-(U14-DO)") (class "Default")
      (node (ref "U14") (pin "5") (pinfunction "DO_5") (pintype "passive"))
      (node (ref "U15") (pin "6") (pinfunction "DIN_6") (pintype "passive"))
    )
    (net (code "113") (name "Net-(U15-DO)") (class "Default")
      (node (ref "U15") (pin "5") (pinfunction "DO_5") (pintype "passive"))
      (node (ref "U16") (pin "6") (pinfunction "DIN_6") (pintype "passive"))
    )
    (net (code "114") (name "Net-(U16-DO)") (class "Default")
      (node (ref "U16") (pin "5") (pinfunction "DO_5") (pintype "passive"))
      (node (ref "U17") (pin "6") (pinfunction "DIN_6") (pintype "passive"))
    )
    (net (code "115") (name "Net-(U17-DO)") (class "Default")
      (node (ref "U17") (pin "5") (pinfunction "DO_5") (pintype "passive"))
      (node (ref "U18") (pin "6") (pinfunction "DIN_6") (pintype "passive"))
    )
    (net (code "116") (name "Net-(U18-DO)") (class "Default")
      (node (ref "U18") (pin "5") (pinfunction "DO_5") (pintype "passive"))
      (node (ref "U19") (pin "6") (pinfunction "DIN_6") (pintype "passive"))
    )
    (net (code "117") (name "Net-(U19-DO)") (class "Default")
      (node (ref "U19") (pin "5") (pinfunction "DO_5") (pintype "passive"))
      (node (ref "U20") (pin "6") (pinfunction "DIN_6") (pintype "passive"))
    )
    (net (code "118") (name "unconnected-(MODE-B-Pad2)") (class "Default")
      (node (ref "MODE") (pin "2") (pinfunction "B_2") (pintype "passive"))
    )
    (net (code "119") (name "unconnected-(P0-Pad1)") (class "Default")
      (node (ref "P0") (pin "1") (pinfunction "1_1") (pintype "passive"))
    )
    (net (code "120") (name "unconnected-(P0-Pad2)") (class "Default")
      (node (ref "P0") (pin "2") (pinfunction "2_2") (pintype "passive"))
    )
    (net (code "121") (name "unconnected-(P0-Pad3)") (class "Default")
      (node (ref "P0") (pin "3") (pinfunction "3_3") (pintype "passive"))
    )
    (net (code "122") (name "unconnected-(P0-Pad4)") (class "Default")
      (node (ref "P0") (pin "4") (pinfunction "4_4") (pintype "passive"))
    )
    (net (code "123") (name "unconnected-(P1-Pad1)") (class "Default")
      (node (ref "P1") (pin "1") (pinfunction "1_1") (pintype "passive"))
    )
    (net (code "124") (name "unconnected-(P1-Pad9)") (class "Default")
      (node (ref "P1") (pin "9") (pinfunction "9_9") (pintype "passive"))
    )
    (net (code "125") (name "unconnected-(P1-Pad10)") (class "Default")
      (node (ref "P1") (pin "10") (pinfunction "10_10") (pintype "passive"))
    )
    (net (code "126") (name "unconnected-(P1-Pad11)") (class "Default")
      (node (ref "P1") (pin "11") (pinfunction "11_11") (pintype "passive"))
    )
    (net (code "127") (name "unconnected-(U20-DO-Pad5)") (class "Default")
      (node (ref "U20") (pin "5") (pinfunction "DO_5") (pintype "passive"))
    )
    (net (code "128") (name "unconnected-(reset-A-Pad1)") (class "Default")
      (node (ref "reset") (pin "1") (pinfunction "A_1") (pintype "passive"))
    )
    (net (code "129") (name "unconnected-(reset-B-Pad2)") (class "Default")
      (node (ref "reset") (pin "2") (pinfunction "B_2") (pintype "passive"))
    )
  )
)
